# Microphone_MAX9814.net
KiCad netlist of a schematic drawn in Altium Designer
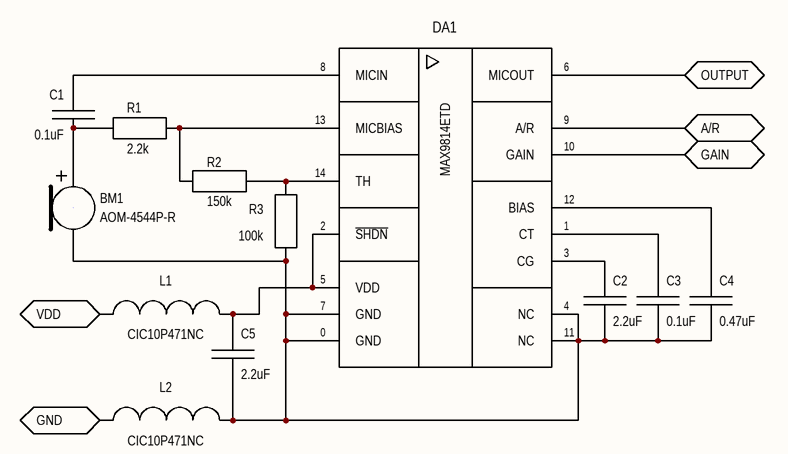
[diagram p0: Microphone MAX9814.SchDoc]

(export (version "E")
  (design (tool "Eeschema 10.0.6"))
  (components
    (comp (ref "BM1")
      (value "AOM-4544P-R")
      (footprint "Electret microphone d9.7x4.5mm")
      (description "Electret microphone d9.4x6.7mm")
      (fields (field (name "MANUFACTURER") "PUI Audio"))
      (libsource (lib "Electro-Mechanical") (part "Electret microphone d9.4x6.7mm"))
    )
    (comp (ref "C1")
      (value "0.1uF")
      (footprint "CAPC1608L")
      (description "Capacitor Ceramic 0.1uF 25V 0603(1608)")
      (fields (field (name "TOLERANCE") "±10%") (field (name "VOLTAGE") "25V"))
      (libsource (lib "Capacitors") (part "Capacitor Ceramic 0.1uF 25V 0603(1608)"))
    )
    (comp (ref "C2")
      (value "2.2uF")
      (footprint "CAPC2012L")
      (description "Capacitor Ceramic 2.2uF 50V 0805(2012)")
      (fields (field (name "TOLERANCE") "±10%") (field (name "VOLTAGE") "50V"))
      (libsource (lib "Capacitors") (part "Capacitor Ceramic 2.2uF 50V 0805(2012)"))
    )
    (comp (ref "C3")
      (value "0.1uF")
      (footprint "CAPC1608L")
      (description "Capacitor Ceramic 0.1uF 25V 0603(1608)")
      (fields (field (name "TOLERANCE") "±10%") (field (name "VOLTAGE") "25V"))
      (libsource (lib "Capacitors") (part "Capacitor Ceramic 0.1uF 25V 0603(1608)"))
    )
    (comp (ref "C4")
      (value "0.47uF")
      (footprint "CAPC1608L")
      (description "Capacitor Ceramic 0.47uF 10V 0603(1608)")
      (fields (field (name "TOLERANCE") "±10%") (field (name "VOLTAGE") "10V"))
      (libsource (lib "Capacitors") (part "Capacitor Ceramic 0.47uF 10V 0603(1608)"))
    )
    (comp (ref "C5")
      (value "2.2uF")
      (footprint "CAPC2012L")
      (description "Capacitor Ceramic 2.2uF 50V 0805(2012)")
      (fields (field (name "TOLERANCE") "±10%") (field (name "VOLTAGE") "50V"))
      (libsource (lib "Capacitors") (part "Capacitor Ceramic 2.2uF 50V 0805(2012)"))
    )
    (comp (ref "DA1")
      (value "MAX9814ETD")
      (footprint "TDFN-EP-14")
      (description "Microphone Amplifier with AGC and Low-Noise Microphone Bias")
      (fields (field (name "MANUFACTURER") "Maxim Integrated"))
      (libsource (lib "ICs") (part "MAX9814ETD"))
    )
    (comp (ref "L1")
      (value "CIC10P471NC")
      (footprint "FB1608L")
      (description "Ferrite Bead 1.2A 470Ohm")
      (fields (field (name "MANUFACTURER") "Samsung Electro-Mechanics America"))
      (libsource (lib "Inductors") (part "CIC10P471NC"))
    )
    (comp (ref "L2")
      (value "CIC10P471NC")
      (footprint "FB1608L")
      (description "Ferrite Bead 1.2A 470Ohm")
      (fields (field (name "MANUFACTURER") "Samsung Electro-Mechanics America"))
      (libsource (lib "Inductors") (part "CIC10P471NC"))
    )
    (comp (ref "R1")
      (value "2.2k")
      (footprint "RESC1608L")
      (description "Resistor Ceramic 2.2k 0.1W 0603(1608)")
      (fields (field (name "TOLERANCE") "±5%") (field (name "POWER") "0.1W"))
      (libsource (lib "Resistors") (part "Resistor Ceramic 2.2k 0.1W 0603(1608)"))
    )
    (comp (ref "R2")
      (value "150k")
      (footprint "RESC1608L")
      (description "Resistor Ceramic 150k 0.1W 0603(1608)")
      (fields (field (name "TOLERANCE") "±5%") (field (name "POWER") "0.1W"))
      (libsource (lib "Resistors") (part "Resistor Ceramic 150k 0.1W 0603(1608)"))
    )
    (comp (ref "R3")
      (value "100k")
      (footprint "RESC1608L")
      (description "Resistor Ceramic 100k 0.1W 0603(1608)")
      (fields (field (name "TOLERANCE") "±5%") (field (name "POWER") "0.1W"))
      (libsource (lib "Resistors") (part "Resistor Ceramic 100k 0.1W 0603(1608)"))
    )
  )
  (nets
    (net (code "1") (name "/A{slash}R") (class "Default")
      (node (ref "DA1") (pin "9") (pinfunction "A/R_9") (pintype "passive"))
    )
    (net (code "2") (name "/GAIN") (class "Default")
      (node (ref "DA1") (pin "10") (pinfunction "GAIN_10") (pintype "passive"))
    )
    (net (code "3") (name "/GND") (class "Default")
      (node (ref "L2") (pin "1") (pinfunction "1_1") (pintype "passive"))
    )
    (net (code "4") (name "/OUTPUT") (class "Default")
      (node (ref "DA1") (pin "6") (pinfunction "MICOUT_6") (pintype "passive"))
    )
    (net (code "5") (name "/VDD") (class "Default")
      (node (ref "L1") (pin "1") (pinfunction "1_1") (pintype "passive"))
    )
    (net (code "6") (name "Net-(BM1-+)") (class "Default")
      (node (ref "BM1") (pin "1") (pinfunction "+_1") (pintype "passive"))
      (node (ref "C1") (pin "2") (pinfunction "2_2") (pintype "passive"))
      (node (ref "R1") (pin "1") (pinfunction "1_1") (pintype "passive"))
    )
    (net (code "7") (name "Net-(BM1--)") (class "Default")
      (node (ref "BM1") (pin "2") (pinfunction "-_2") (pintype "passive"))
      (node (ref "C2") (pin "2") (pinfunction "2_2") (pintype "passive"))
      (node (ref "C3") (pin "2") (pinfunction "2_2") (pintype "passive"))
      (node (ref "C4") (pin "2") (pinfunction "2_2") (pintype "passive"))
      (node (ref "C5") (pin "2") (pinfunction "2_2") (pintype "passive"))
      (node (ref "DA1") (pin "0") (pinfunction "GND_0") (pintype "passive"))
      (node (ref "DA1") (pin "11") (pinfunction "NC_11") (pintype "passive"))
      (node (ref "DA1") (pin "4") (pinfunction "NC_4") (pintype "passive"))
      (node (ref "DA1") (pin "7") (pinfunction "GND_7") (pintype "passive"))
      (node (ref "L2") (pin "2") (pinfunction "2_2") (pintype "passive"))
      (node (ref "R3") (pin "2") (pinfunction "2_2") (pintype "passive"))
    )
    (net (code "8") (name "Net-(DA1-BIAS)") (class "Default")
      (node (ref "C4") (pin "1") (pinfunction "1_1") (pintype "passive"))
      (node (ref "DA1") (pin "12") (pinfunction "BIAS_12") (pintype "passive"))
    )
    (net (code "9") (name "Net-(DA1-CG)") (class "Default")
      (node (ref "C2") (pin "1") (pinfunction "1_1") (pintype "passive"))
      (node (ref "DA1") (pin "3") (pinfunction "CG_3") (pintype "passive"))
    )
    (net (code "10") (name "Net-(DA1-CT)") (class "Default")
      (node (ref "C3") (pin "1") (pinfunction "1_1") (pintype "passive"))
      (node (ref "DA1") (pin "1") (pinfunction "CT_1") (pintype "passive"))
    )
    (net (code "11") (name "Net-(DA1-MICBIAS)") (class "Default")
      (node (ref "DA1") (pin "13") (pinfunction "MICBIAS_13") (pintype "passive"))
      (node (ref "R1") (pin "2") (pinfunction "2_2") (pintype "passive"))
      (node (ref "R2") (pin "2") (pinfunction "2_2") (pintype "passive"))
    )
    (net (code "12") (name "Net-(DA1-MICIN)") (class "Default")
      (node (ref "C1") (pin "1") (pinfunction "1_1") (pintype "passive"))
      (node (ref "DA1") (pin "8") (pinfunction "MICIN_8") (pintype "passive"))
    )
    (net (code "13") (name "Net-(DA1-TH)") (class "Default")
      (node (ref "DA1") (pin "14") (pinfunction "TH_14") (pintype "passive"))
      (node (ref "R2") (pin "1") (pinfunction "1_1") (pintype "passive"))
      (node (ref "R3") (pin "1") (pinfunction "1_1") (pintype "passive"))
    )
    (net (code "14") (name "Net-(DA1-VDD)") (class "Default")
      (node (ref "C5") (pin "1") (pinfunction "1_1") (pintype "passive"))
      (node (ref "DA1") (pin "2") (pinfunction "~{SHDN}_2") (pintype "passive"))
      (node (ref "DA1") (pin "5") (pinfunction "VDD_5") (pintype "passive"))
      (node (ref "L1") (pin "2") (pinfunction "2_2") (pintype "passive"))
    )
  )
)
